# SixAxIMU_VN.net
KiCad netlist of a schematic drawn in Altium Designer
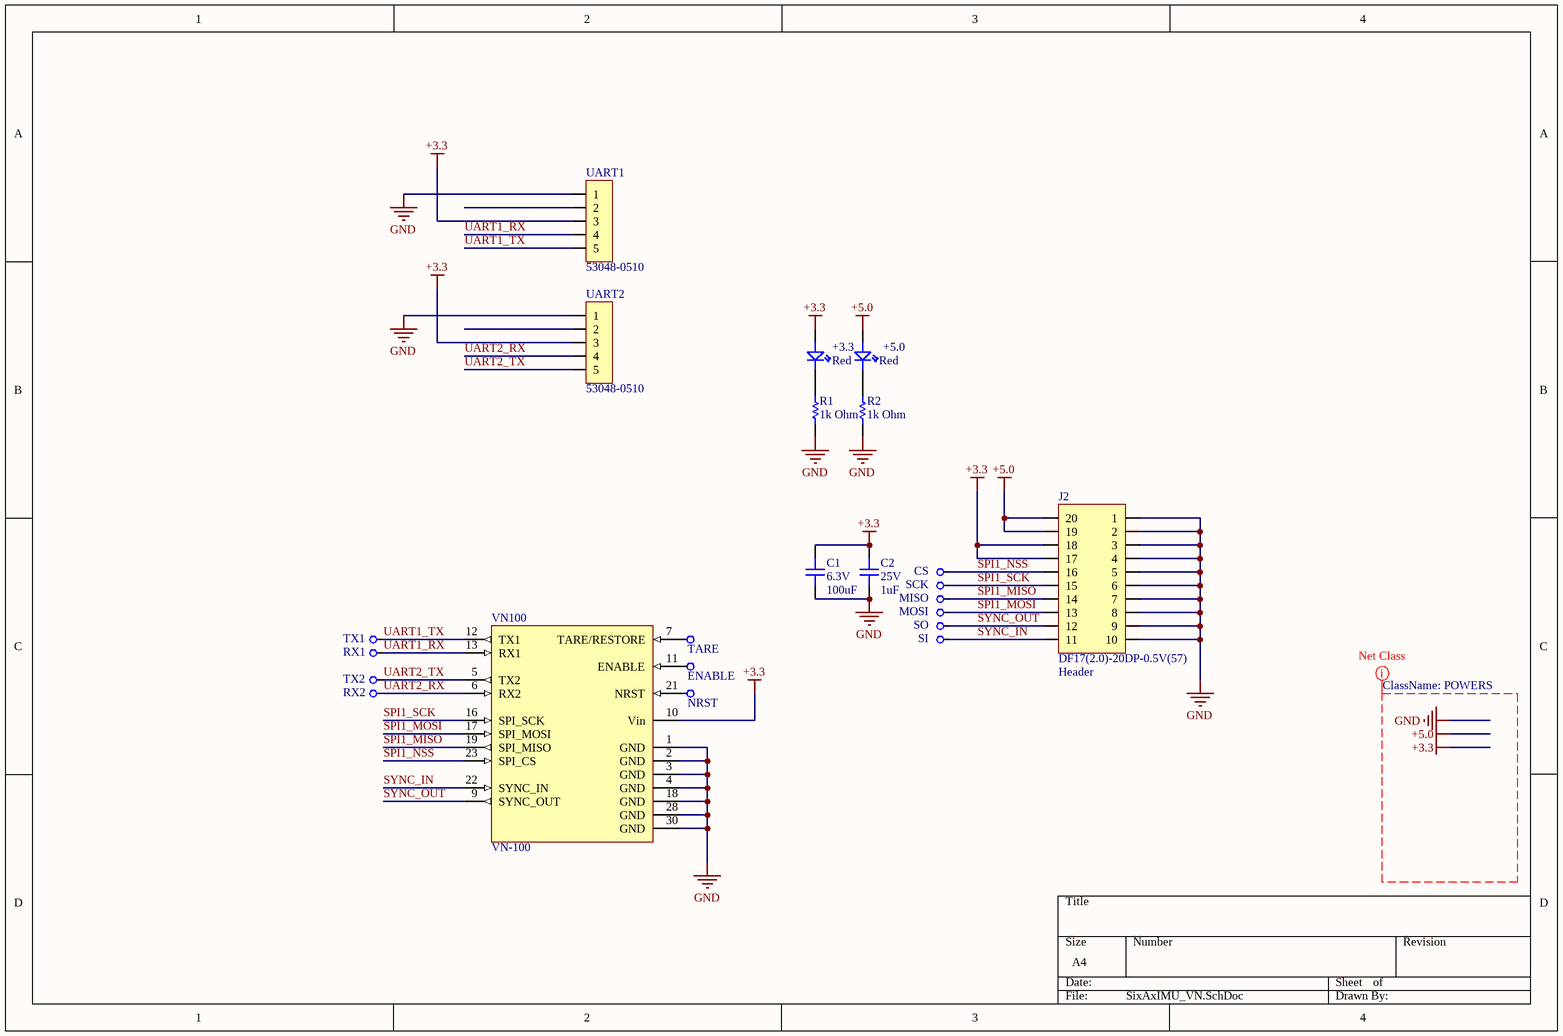
[diagram p0: SixAxIMU_VN.SchDoc]

(export (version "E")
  (design (tool "Eeschema 10.0.6"))
  (components
    (comp (ref "+3.3")
      (value "Red")
      (footprint "LED 0603")
      (description "LED, Red, 0603")
      (fields (field (name "MANUFACTURER PART NUMBER") "1608SURC-06"))
      (libsource (lib "NaniBox") (part "1608SURC-06"))
    )
    (comp (ref "+5.0")
      (value "Red")
      (footprint "LED 0603")
      (description "LED, Red, 0603")
      (fields (field (name "MANUFACTURER PART NUMBER") "1608SURC-06"))
      (libsource (lib "NaniBox") (part "1608SURC-06"))
    )
    (comp (ref "C1")
      (value "100uF")
      (footprint "CAP 1206")
      (description "MLCC, 100uF, 1206, 20%, 6.3V, X5R")
      (fields
        (field (name "MANUFACTURER") "Samsung")
        (field (name "MANUFACTURER PART NUMBER") "CL31A107MQHNNNE")
        (field (name "VOLTAGE RATING") "6.3V")
      )
      (libsource (lib "NaniBox") (part "CL31A107MQHNNNE"))
    )
    (comp (ref "C2")
      (value "1uF")
      (footprint "CAP 0603")
      (description "MLCC, 1uF, 0603, 10%, 25V, X5R")
      (fields
        (field (name "MANUFACTURER") "Samsung")
        (field (name "MANUFACTURER PART NUMBER") "CL10A105KA8NNNC")
        (field (name "VOLTAGE RATING") "25V")
      )
      (libsource (lib "NaniBox") (part "CL10A105KA8NNNC"))
    )
    (comp (ref "CS")
      (value "TEST")
      (footprint "TEST_0.5mm, SMD")
      (libsource (lib "NaniBox_Conn") (part "TEST"))
    )
    (comp (ref "ENABLE")
      (value "TEST")
      (footprint "TEST_0.5mm, SMD")
      (libsource (lib "NaniBox_Conn") (part "TEST"))
    )
    (comp (ref "J2")
      (value "DF17(2.0)-20DP-0.5V(57)")
      (footprint "DF17(2.0)-20DP-0.5V(57)")
      (description "Conn, B2B, 20 Pos, HEADER")
      (fields (field (name "MANUFACTURER") "Hirose") (field (name "TYPE") "Header"))
      (libsource (lib "NaniBox") (part "DF17(2.0)-20DP-0.5V(57)"))
    )
    (comp (ref "MISO")
      (value "TEST")
      (footprint "TEST_0.5mm, SMD")
      (libsource (lib "NaniBox_Conn") (part "TEST"))
    )
    (comp (ref "MOSI")
      (value "TEST")
      (footprint "TEST_0.5mm, SMD")
      (libsource (lib "NaniBox_Conn") (part "TEST"))
    )
    (comp (ref "NRST")
      (value "TEST")
      (footprint "TEST_0.5mm, SMD")
      (libsource (lib "NaniBox_Conn") (part "TEST"))
    )
    (comp (ref "R1")
      (value "1k Ohm")
      (footprint "RES 0402")
      (description "RES, 0402, 1k, 1%")
      (fields
        (field (name "MANUFACTURER") "Yageo")
        (field (name "MANUFACTURER PART NUMBER") "P311-1.00KLRTR-ND")
      )
      (libsource (lib "NaniBox") (part "P311-1.00KLRTR-ND"))
    )
    (comp (ref "R2")
      (value "1k Ohm")
      (footprint "RES 0402")
      (description "RES, 0402, 1k, 1%")
      (fields
        (field (name "MANUFACTURER") "Yageo")
        (field (name "MANUFACTURER PART NUMBER") "P311-1.00KLRTR-ND")
      )
      (libsource (lib "NaniBox") (part "P311-1.00KLRTR-ND"))
    )
    (comp (ref "RX1")
      (value "TEST")
      (footprint "TEST_0.5mm, SMD")
      (libsource (lib "NaniBox_Conn") (part "TEST"))
    )
    (comp (ref "RX2")
      (value "TEST")
      (footprint "TEST_0.5mm, SMD")
      (libsource (lib "NaniBox_Conn") (part "TEST"))
    )
    (comp (ref "SCK")
      (value "TEST")
      (footprint "TEST_0.5mm, SMD")
      (libsource (lib "NaniBox_Conn") (part "TEST"))
    )
    (comp (ref "SI")
      (value "TEST")
      (footprint "TEST_0.5mm, SMD")
      (libsource (lib "NaniBox_Conn") (part "TEST"))
    )
    (comp (ref "SO")
      (value "TEST")
      (footprint "TEST_0.5mm, SMD")
      (libsource (lib "NaniBox_Conn") (part "TEST"))
    )
    (comp (ref "TARE")
      (value "TEST")
      (footprint "TEST_0.5mm, SMD")
      (libsource (lib "NaniBox_Conn") (part "TEST"))
    )
    (comp (ref "TX1")
      (value "TEST")
      (footprint "TEST_0.5mm, SMD")
      (libsource (lib "NaniBox_Conn") (part "TEST"))
    )
    (comp (ref "TX2")
      (value "TEST")
      (footprint "TEST_0.5mm, SMD")
      (libsource (lib "NaniBox_Conn") (part "TEST"))
    )
    (comp (ref "UART1")
      (value "53048-0510")
      (footprint "PicoBlade, 53048-0510")
      (description "PicoBlade, Header, R/A, PTH, 5 Pos, 1.25mm Pitch")
      (fields (field (name "MANUFACTURER") "Molex"))
      (libsource (lib "NaniBox_Conn") (part "53048-0510"))
    )
    (comp (ref "UART2")
      (value "53048-0510")
      (footprint "PicoBlade, 53048-0510")
      (description "PicoBlade, Header, R/A, PTH, 5 Pos, 1.25mm Pitch")
      (fields (field (name "MANUFACTURER") "Molex"))
      (libsource (lib "NaniBox_Conn") (part "53048-0510"))
    )
    (comp (ref "VN100")
      (value "VN-100")
      (footprint "VN-100")
      (description "Vector Nav SMD IMU/AHRS")
      (fields (field (name "MANUFACTURER") "Vector Nav"))
      (libsource (lib "NaniBox") (part "VN-100"))
    )
  )
  (nets
    (net (code "1") (name "+3.3") (class "Default")
      (node (ref "+3.3") (pin "A") (pinfunction "A_A") (pintype "power_in"))
      (node (ref "C1") (pin "2") (pinfunction "2_2") (pintype "passive"))
      (node (ref "C2") (pin "2") (pinfunction "2_2") (pintype "passive"))
      (node (ref "J2") (pin "17") (pinfunction "17_17") (pintype "passive"))
      (node (ref "J2") (pin "18") (pinfunction "18_18") (pintype "passive"))
      (node (ref "UART1") (pin "3") (pinfunction "3_3") (pintype "passive"))
      (node (ref "UART2") (pin "3") (pinfunction "3_3") (pintype "passive"))
      (node (ref "VN100") (pin "10") (pinfunction "Vin_10") (pintype "power_in"))
    )
    (net (code "2") (name "+5.0") (class "Default")
      (node (ref "+5.0") (pin "A") (pinfunction "A_A") (pintype "power_in"))
      (node (ref "J2") (pin "19") (pinfunction "19_19") (pintype "passive"))
      (node (ref "J2") (pin "20") (pinfunction "20_20") (pintype "passive"))
    )
    (net (code "3") (name "/SPI1_MISO") (class "Default")
      (node (ref "J2") (pin "14") (pinfunction "14_14") (pintype "passive"))
      (node (ref "MISO") (pin "0") (pinfunction "0_0") (pintype "passive"))
      (node (ref "VN100") (pin "19") (pinfunction "SPI_MISO_19") (pintype "output"))
    )
    (net (code "4") (name "/SPI1_MOSI") (class "Default")
      (node (ref "J2") (pin "13") (pinfunction "13_13") (pintype "passive"))
      (node (ref "MOSI") (pin "0") (pinfunction "0_0") (pintype "passive"))
      (node (ref "VN100") (pin "17") (pinfunction "SPI_MOSI_17") (pintype "input"))
    )
    (net (code "5") (name "/SPI1_NSS") (class "Default")
      (node (ref "CS") (pin "0") (pinfunction "0_0") (pintype "passive"))
      (node (ref "J2") (pin "16") (pinfunction "16_16") (pintype "passive"))
      (node (ref "VN100") (pin "23") (pinfunction "SPI_CS_23") (pintype "input"))
    )
    (net (code "6") (name "/SPI1_SCK") (class "Default")
      (node (ref "J2") (pin "15") (pinfunction "15_15") (pintype "passive"))
      (node (ref "SCK") (pin "0") (pinfunction "0_0") (pintype "passive"))
      (node (ref "VN100") (pin "16") (pinfunction "SPI_SCK_16") (pintype "input"))
    )
    (net (code "7") (name "/SYNC_IN") (class "Default")
      (node (ref "J2") (pin "11") (pinfunction "11_11") (pintype "passive"))
      (node (ref "SI") (pin "0") (pinfunction "0_0") (pintype "passive"))
      (node (ref "VN100") (pin "22") (pinfunction "SYNC_IN_22") (pintype "input"))
    )
    (net (code "8") (name "/SYNC_OUT") (class "Default")
      (node (ref "J2") (pin "12") (pinfunction "12_12") (pintype "passive"))
      (node (ref "SO") (pin "0") (pinfunction "0_0") (pintype "passive"))
      (node (ref "VN100") (pin "9") (pinfunction "SYNC_OUT_9") (pintype "output"))
    )
    (net (code "9") (name "/UART1_RX") (class "Default")
      (node (ref "RX1") (pin "0") (pinfunction "0_0") (pintype "passive"))
      (node (ref "UART1") (pin "4") (pinfunction "4_4") (pintype "passive"))
      (node (ref "VN100") (pin "13") (pinfunction "RX1_13") (pintype "input"))
    )
    (net (code "10") (name "/UART1_TX") (class "Default")
      (node (ref "TX1") (pin "0") (pinfunction "0_0") (pintype "passive"))
      (node (ref "UART1") (pin "5") (pinfunction "5_5") (pintype "passive"))
      (node (ref "VN100") (pin "12") (pinfunction "TX1_12") (pintype "output"))
    )
    (net (code "11") (name "/UART2_RX") (class "Default")
      (node (ref "RX2") (pin "0") (pinfunction "0_0") (pintype "passive"))
      (node (ref "UART2") (pin "4") (pinfunction "4_4") (pintype "passive"))
      (node (ref "VN100") (pin "6") (pinfunction "RX2_6") (pintype "input"))
    )
    (net (code "12") (name "/UART2_TX") (class "Default")
      (node (ref "TX2") (pin "0") (pinfunction "0_0") (pintype "passive"))
      (node (ref "UART2") (pin "5") (pinfunction "5_5") (pintype "passive"))
      (node (ref "VN100") (pin "5") (pinfunction "TX2_5") (pintype "output"))
    )
    (net (code "13") (name "GND") (class "Default")
      (node (ref "C1") (pin "1") (pinfunction "1_1") (pintype "passive"))
      (node (ref "C2") (pin "1") (pinfunction "1_1") (pintype "passive"))
      (node (ref "J2") (pin "1") (pinfunction "1_1") (pintype "passive"))
      (node (ref "J2") (pin "10") (pinfunction "10_10") (pintype "passive"))
      (node (ref "J2") (pin "2") (pinfunction "2_2") (pintype "passive"))
      (node (ref "J2") (pin "3") (pinfunction "3_3") (pintype "passive"))
      (node (ref "J2") (pin "4") (pinfunction "4_4") (pintype "passive"))
      (node (ref "J2") (pin "5") (pinfunction "5_5") (pintype "passive"))
      (node (ref "J2") (pin "6") (pinfunction "6_6") (pintype "passive"))
      (node (ref "J2") (pin "7") (pinfunction "7_7") (pintype "passive"))
      (node (ref "J2") (pin "8") (pinfunction "8_8") (pintype "passive"))
      (node (ref "J2") (pin "9") (pinfunction "9_9") (pintype "passive"))
      (node (ref "R1") (pin "1") (pinfunction "1_1") (pintype "passive"))
      (node (ref "R2") (pin "1") (pinfunction "1_1") (pintype "passive"))
      (node (ref "UART1") (pin "1") (pinfunction "1_1") (pintype "passive"))
      (node (ref "UART2") (pin "1") (pinfunction "1_1") (pintype "passive"))
      (node (ref "VN100") (pin "1") (pinfunction "GND_1") (pintype "power_in"))
      (node (ref "VN100") (pin "18") (pinfunction "GND_18") (pintype "power_in"))
      (node (ref "VN100") (pin "2") (pinfunction "GND_2") (pintype "power_in"))
      (node (ref "VN100") (pin "28") (pinfunction "GND_28") (pintype "power_in"))
      (node (ref "VN100") (pin "3") (pinfunction "GND_3") (pintype "power_in"))
      (node (ref "VN100") (pin "30") (pinfunction "GND_30") (pintype "power_in"))
      (node (ref "VN100") (pin "4") (pinfunction "GND_4") (pintype "power_in"))
    )
    (net (code "14") (name "Net-(+3.3-PadK)") (class "Default")
      (node (ref "+3.3") (pin "K") (pinfunction "K_K") (pintype "power_in"))
      (node (ref "R1") (pin "2") (pinfunction "2_2") (pintype "passive"))
    )
    (net (code "15") (name "Net-(+5.0-PadK)") (class "Default")
      (node (ref "+5.0") (pin "K") (pinfunction "K_K") (pintype "power_in"))
      (node (ref "R2") (pin "2") (pinfunction "2_2") (pintype "passive"))
    )
    (net (code "16") (name "Net-(VN100-ENABLE)") (class "Default")
      (node (ref "ENABLE") (pin "0") (pinfunction "0_0") (pintype "passive"))
      (node (ref "VN100") (pin "11") (pinfunction "ENABLE_11") (pintype "input"))
    )
    (net (code "17") (name "Net-(VN100-NRST)") (class "Default")
      (node (ref "NRST") (pin "0") (pinfunction "0_0") (pintype "passive"))
      (node (ref "VN100") (pin "21") (pinfunction "NRST_21") (pintype "input"))
    )
    (net (code "18") (name "Net-(VN100-TARE{slash}RESTORE)") (class "Default")
      (node (ref "TARE") (pin "0") (pinfunction "0_0") (pintype "passive"))
      (node (ref "VN100") (pin "7") (pinfunction "TARE/RESTORE_7") (pintype "input"))
    )
    (net (code "19") (name "unconnected-(UART1-Pad2)") (class "Default")
      (node (ref "UART1") (pin "2") (pinfunction "2_2") (pintype "passive"))
    )
    (net (code "20") (name "unconnected-(UART2-Pad2)") (class "Default")
      (node (ref "UART2") (pin "2") (pinfunction "2_2") (pintype "passive"))
    )
  )
)
